# FPGA_MIO.net
KiCad netlist of a schematic drawn in Altium Designer
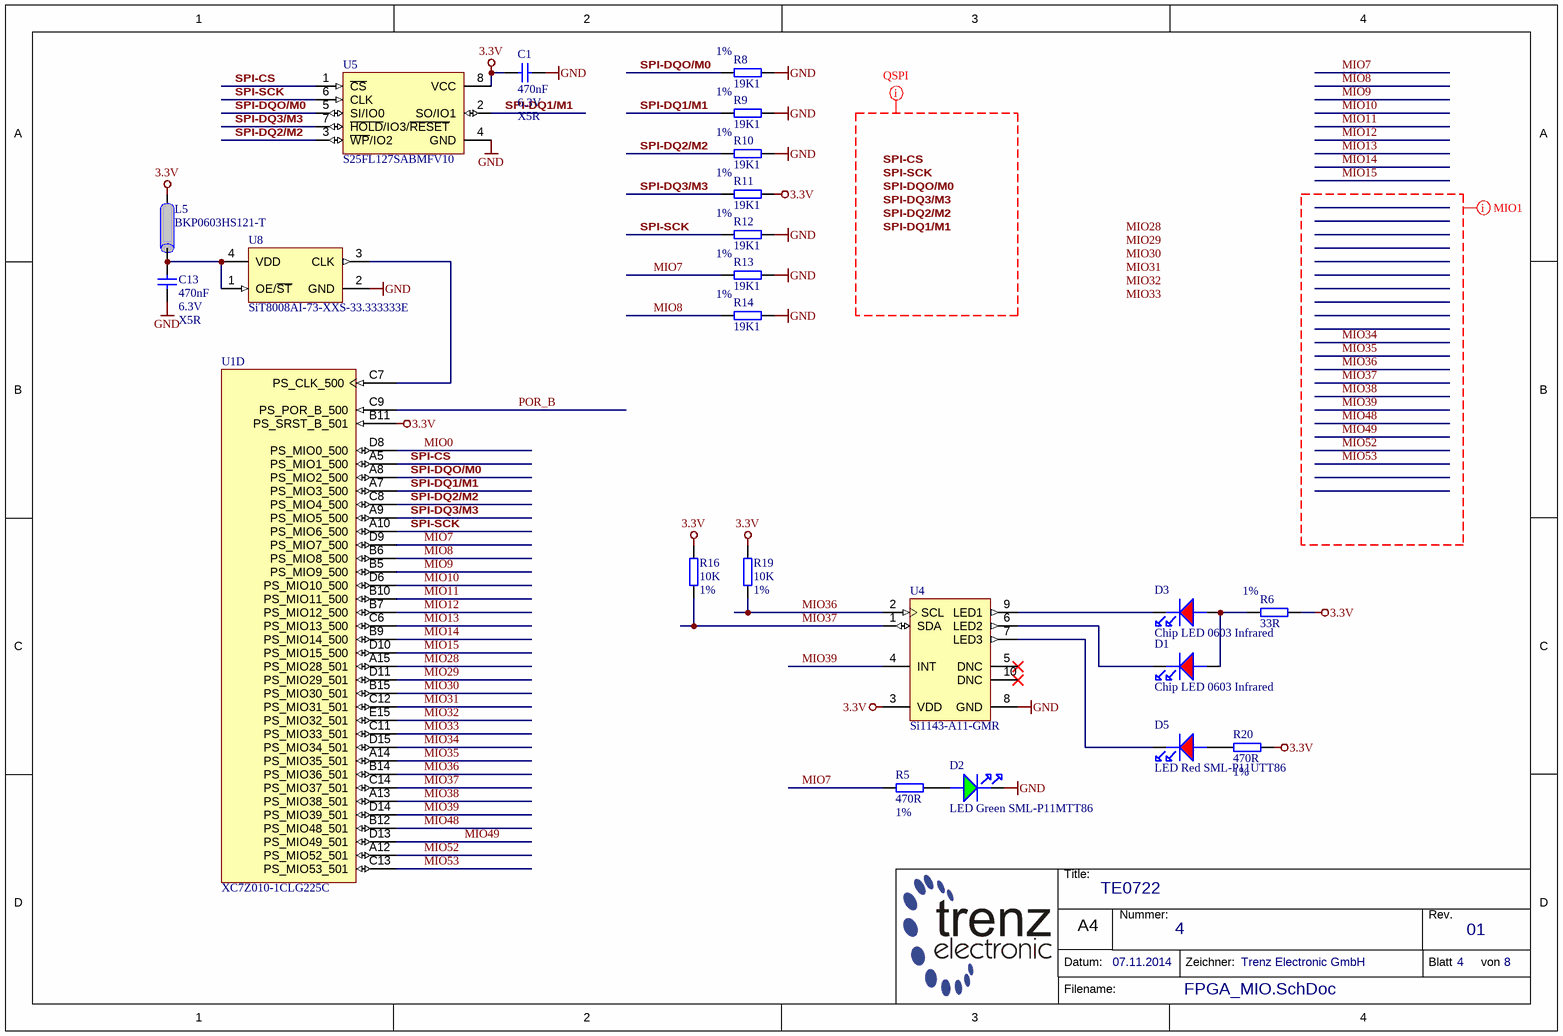
[diagram p0: FPGA_MIO.SchDoc]

(export (version "E")
  (design (tool "Eeschema 10.0.6"))
  (components
    (comp (ref "C1")
      (value "470nF")
      (footprint "CAPC0603X33N")
      (description "KON 470nF X5R 6.3V SMD 20%")
      (fields
        (field (name "VOLTAGE") "6.3V")
        (field (name "TECHNOLOGY") "X5R")
        (field (name "TOLERANCE") "20%")
      )
      (libsource (lib "TE") (part "CAP-NP"))
    )
    (comp (ref "C13")
      (value "470nF")
      (footprint "CAPC0603X33N")
      (description "KON 470nF X5R 6.3V SMD 20%")
      (fields
        (field (name "VOLTAGE") "6.3V")
        (field (name "TECHNOLOGY") "X5R")
        (field (name "TOLERANCE") "20%")
      )
      (libsource (lib "TE") (part "CAP-NP"))
    )
    (comp (ref "D1")
      (value "Chip LED 0603 Infrared")
      (footprint "chipLED_0603_Red")
      (fields (field (name "VOLTAGE") "1.2"))
      (libsource (lib "TE") (part "LED_ROT"))
    )
    (comp (ref "D2")
      (value "LED Green SML-P11MTT86")
      (footprint "LEDC1006X25N_GREEN")
      (description "LED Grün SML-P11MTT86 SMD")
      (libsource (lib "TE") (part "LED_GRUEN"))
    )
    (comp (ref "D3")
      (value "Chip LED 0603 Infrared")
      (footprint "chipLED_0603_Red")
      (fields (field (name "VOLTAGE") "1.2"))
      (libsource (lib "TE") (part "LED_ROT"))
    )
    (comp (ref "D5")
      (value "LED Red SML-P11UTT86")
      (footprint "LEDC1006X25N_RED")
      (description "LED Rot SML-P11UTT86 SMD")
      (libsource (lib "TE") (part "LED_ROT"))
    )
    (comp (ref "L5")
      (value "BKP0603HS121-T")
      (footprint "INDC0603X33N")
      (description "Ferritdurchführung SMD 0201")
      (fields (field (name "TOLERANCE") "25%"))
      (libsource (lib "TE") (part "Ferritperle"))
    )
    (comp (ref "R5")
      (value "470R")
      (footprint "RESC1005X40N")
      (description "WID SMD 470R 1% 0,063W")
      (fields (field (name "TOLERANCE") "1%"))
      (libsource (lib "TE") (part "RES"))
    )
    (comp (ref "R6")
      (value "33R")
      (footprint "RESC1005X40N")
      (description "WID SMD 33R 1% 0,063W")
      (fields (field (name "TOLERANCE") "1%"))
      (libsource (lib "TE") (part "RES"))
    )
    (comp (ref "R8")
      (value "19K1")
      (footprint "RESC0603X26N")
      (description "WID SMD 19K1 1% 0,05W")
      (fields (field (name "TOLERANCE") "1%"))
      (libsource (lib "TE") (part "RES"))
    )
    (comp (ref "R9")
      (value "19K1")
      (footprint "RESC0603X26N")
      (description "WID SMD 19K1 1% 0,05W")
      (fields (field (name "TOLERANCE") "1%"))
      (libsource (lib "TE") (part "RES"))
    )
    (comp (ref "R10")
      (value "19K1")
      (footprint "RESC0603X26N")
      (description "WID SMD 19K1 1% 0,05W")
      (fields (field (name "TOLERANCE") "1%"))
      (libsource (lib "TE") (part "RES"))
    )
    (comp (ref "R11")
      (value "19K1")
      (footprint "RESC0603X26N")
      (description "WID SMD 19K1 1% 0,05W")
      (fields (field (name "TOLERANCE") "1%"))
      (libsource (lib "TE") (part "RES"))
    )
    (comp (ref "R12")
      (value "19K1")
      (footprint "RESC0603X26N")
      (description "WID SMD 19K1 1% 0,05W")
      (fields (field (name "TOLERANCE") "1%"))
      (libsource (lib "TE") (part "RES"))
    )
    (comp (ref "R13")
      (value "19K1")
      (footprint "RESC0603X26N")
      (description "WID SMD 19K1 1% 0,05W")
      (fields (field (name "TOLERANCE") "1%"))
      (libsource (lib "TE") (part "RES"))
    )
    (comp (ref "R14")
      (value "19K1")
      (footprint "RESC0603X26N")
      (description "WID SMD 19K1 1% 0,05W")
      (fields (field (name "TOLERANCE") "1%"))
      (libsource (lib "TE") (part "RES"))
    )
    (comp (ref "R16")
      (value "10K")
      (footprint "RESC0603X26N")
      (description "WID SMD 10K 1% 0,05W")
      (fields (field (name "TOLERANCE") "1%"))
      (libsource (lib "TE") (part "RES"))
    )
    (comp (ref "R19")
      (value "10K")
      (footprint "RESC0603X26N")
      (description "WID SMD 10K 1% 0,05W")
      (fields (field (name "TOLERANCE") "1%"))
      (libsource (lib "TE") (part "RES"))
    )
    (comp (ref "R20")
      (value "470R")
      (footprint "RESC1005X40N")
      (description "WID SMD 470R 1% 0,063W")
      (fields (field (name "TOLERANCE") "1%"))
      (libsource (lib "TE") (part "RES"))
    )
    (comp (ref "U1")
      (value "XC7Z010-1CLG225C")
      (footprint "CLG225")
      (libsource (lib "TE") (part "XC7Z010-CLG225"))
    )
    (comp (ref "U4")
      (value "Si1143-A11-GMR")
      (footprint "QFN50P200X200X75-10N")
      (libsource (lib "TE") (part "Si1143"))
    )
    (comp (ref "U5")
      (value "S25FL127SABMFV10")
      (footprint "SOIC127P790X216-8N")
      (description "S25FL127SABMFV10 automotive SO8")
      (libsource (lib "TE") (part "S25FL127S-SO8"))
    )
    (comp (ref "U8")
      (value "SiT8008AI-73-XXS-33.333333E")
      (footprint "2016")
      (description "SiT8008AI-73-XXS-33.333333E MEMS Oszillator 33.333333MHz")
      (libsource (lib "TE") (part "SiT8103"))
    )
  )
  (nets
    (net (code "1") (name "/MIO0") (class "Default")
      (node (ref "U1") (pin "D8") (pinfunction "PS_MIO0_500_D8") (pintype "bidirectional"))
    )
    (net (code "2") (name "/MIO7") (class "Default")
      (node (ref "R13") (pin "1") (pinfunction "1_1") (pintype "passive"))
      (node (ref "R5") (pin "2") (pinfunction "2_2") (pintype "passive"))
      (node (ref "U1") (pin "D9") (pinfunction "PS_MIO7_500_D9") (pintype "bidirectional"))
    )
    (net (code "3") (name "/MIO8") (class "Default")
      (node (ref "R14") (pin "1") (pinfunction "1_1") (pintype "passive"))
      (node (ref "U1") (pin "B6") (pinfunction "PS_MIO8_500_B6") (pintype "bidirectional"))
    )
    (net (code "4") (name "/MIO9") (class "Default")
      (node (ref "U1") (pin "B5") (pinfunction "PS_MIO9_500_B5") (pintype "bidirectional"))
    )
    (net (code "5") (name "/MIO10") (class "Default")
      (node (ref "U1") (pin "D6") (pinfunction "PS_MIO10_500_D6") (pintype "bidirectional"))
    )
    (net (code "6") (name "/MIO11") (class "Default")
      (node (ref "U1") (pin "B10") (pinfunction "PS_MIO11_500_B10") (pintype "bidirectional"))
    )
    (net (code "7") (name "/MIO12") (class "Default")
      (node (ref "U1") (pin "B7") (pinfunction "PS_MIO12_500_B7") (pintype "bidirectional"))
    )
    (net (code "8") (name "/MIO13") (class "Default")
      (node (ref "U1") (pin "C6") (pinfunction "PS_MIO13_500_C6") (pintype "bidirectional"))
    )
    (net (code "9") (name "/MIO14") (class "Default")
      (node (ref "U1") (pin "B9") (pinfunction "PS_MIO14_500_B9") (pintype "bidirectional"))
    )
    (net (code "10") (name "/MIO15") (class "Default")
      (node (ref "U1") (pin "D10") (pinfunction "PS_MIO15_500_D10") (pintype "bidirectional"))
    )
    (net (code "11") (name "/MIO28") (class "Default")
      (node (ref "U1") (pin "A15") (pinfunction "PS_MIO28_501_A15") (pintype "bidirectional"))
    )
    (net (code "12") (name "/MIO29") (class "Default")
      (node (ref "U1") (pin "D11") (pinfunction "PS_MIO29_501_D11") (pintype "bidirectional"))
    )
    (net (code "13") (name "/MIO30") (class "Default")
      (node (ref "U1") (pin "B15") (pinfunction "PS_MIO30_501_B15") (pintype "bidirectional"))
    )
    (net (code "14") (name "/MIO31") (class "Default")
      (node (ref "U1") (pin "C12") (pinfunction "PS_MIO31_501_C12") (pintype "bidirectional"))
    )
    (net (code "15") (name "/MIO32") (class "Default")
      (node (ref "U1") (pin "E15") (pinfunction "PS_MIO32_501_E15") (pintype "bidirectional"))
    )
    (net (code "16") (name "/MIO33") (class "Default")
      (node (ref "U1") (pin "C11") (pinfunction "PS_MIO33_501_C11") (pintype "bidirectional"))
    )
    (net (code "17") (name "/MIO34") (class "Default")
      (node (ref "U1") (pin "D15") (pinfunction "PS_MIO34_501_D15") (pintype "bidirectional"))
    )
    (net (code "18") (name "/MIO35") (class "Default")
      (node (ref "U1") (pin "A14") (pinfunction "PS_MIO35_501_A14") (pintype "bidirectional"))
    )
    (net (code "19") (name "/MIO36") (class "Default")
      (node (ref "R19") (pin "1") (pinfunction "1_1") (pintype "passive"))
      (node (ref "U1") (pin "B14") (pinfunction "PS_MIO36_501_B14") (pintype "bidirectional"))
      (node (ref "U4") (pin "2") (pinfunction "SCL_2") (pintype "input"))
    )
    (net (code "20") (name "/MIO37") (class "Default")
      (node (ref "R16") (pin "1") (pinfunction "1_1") (pintype "passive"))
      (node (ref "U1") (pin "C14") (pinfunction "PS_MIO37_501_C14") (pintype "bidirectional"))
      (node (ref "U4") (pin "1") (pinfunction "SDA_1") (pintype "bidirectional"))
    )
    (net (code "21") (name "/MIO38") (class "Default")
      (node (ref "U1") (pin "A13") (pinfunction "PS_MIO38_501_A13") (pintype "bidirectional"))
    )
    (net (code "22") (name "/MIO39") (class "Default")
      (node (ref "U1") (pin "D14") (pinfunction "PS_MIO39_501_D14") (pintype "bidirectional"))
      (node (ref "U4") (pin "4") (pinfunction "INT_4") (pintype "open_collector"))
    )
    (net (code "23") (name "/MIO48") (class "Default")
      (node (ref "U1") (pin "B12") (pinfunction "PS_MIO48_501_B12") (pintype "bidirectional"))
    )
    (net (code "24") (name "/MIO49") (class "Default")
      (node (ref "U1") (pin "D13") (pinfunction "PS_MIO49_501_D13") (pintype "bidirectional"))
    )
    (net (code "25") (name "/MIO52") (class "Default")
      (node (ref "U1") (pin "A12") (pinfunction "PS_MIO52_501_A12") (pintype "bidirectional"))
    )
    (net (code "26") (name "/MIO53") (class "Default")
      (node (ref "U1") (pin "C13") (pinfunction "PS_MIO53_501_C13") (pintype "bidirectional"))
    )
    (net (code "27") (name "/POR_B") (class "Default")
      (node (ref "U1") (pin "C9") (pinfunction "PS_POR_B_500_C9") (pintype "input"))
    )
    (net (code "28") (name "/SPI-CS") (class "Default")
      (node (ref "U1") (pin "A5") (pinfunction "PS_MIO1_500_A5") (pintype "bidirectional"))
      (node (ref "U5") (pin "1") (pinfunction "~{CS}_1") (pintype "input"))
    )
    (net (code "29") (name "/SPI-DQ1{slash}M1") (class "Default")
      (node (ref "R9") (pin "1") (pinfunction "1_1") (pintype "passive"))
      (node (ref "U1") (pin "A7") (pinfunction "PS_MIO3_500_A7") (pintype "bidirectional"))
      (node (ref "U5") (pin "2") (pinfunction "SO/IO1_2") (pintype "bidirectional"))
    )
    (net (code "30") (name "/SPI-DQ2{slash}M2") (class "Default")
      (node (ref "R10") (pin "1") (pinfunction "1_1") (pintype "passive"))
      (node (ref "U1") (pin "C8") (pinfunction "PS_MIO4_500_C8") (pintype "bidirectional"))
      (node (ref "U5") (pin "3") (pinfunction "~{WP}/IO2_3") (pintype "bidirectional"))
    )
    (net (code "31") (name "/SPI-DQ3{slash}M3") (class "Default")
      (node (ref "R11") (pin "1") (pinfunction "1_1") (pintype "passive"))
      (node (ref "U1") (pin "A9") (pinfunction "PS_MIO5_500_A9") (pintype "bidirectional"))
      (node (ref "U5") (pin "7") (pinfunction "~{HOLD}/IO3/~{RESET}_7") (pintype "bidirectional"))
    )
    (net (code "32") (name "/SPI-DQO{slash}M0") (class "Default")
      (node (ref "R8") (pin "1") (pinfunction "1_1") (pintype "passive"))
      (node (ref "U1") (pin "A8") (pinfunction "PS_MIO2_500_A8") (pintype "bidirectional"))
      (node (ref "U5") (pin "5") (pinfunction "SI/IO0_5") (pintype "bidirectional"))
    )
    (net (code "33") (name "/SPI-SCK") (class "Default")
      (node (ref "R12") (pin "1") (pinfunction "1_1") (pintype "passive"))
      (node (ref "U1") (pin "A10") (pinfunction "PS_MIO6_500_A10") (pintype "bidirectional"))
      (node (ref "U5") (pin "6") (pinfunction "CLK_6") (pintype "input"))
    )
    (net (code "34") (name "3.3V") (class "Default")
      (node (ref "C1") (pin "1") (pinfunction "1_1") (pintype "passive"))
      (node (ref "L5") (pin "1") (pinfunction "1_1") (pintype "passive"))
      (node (ref "R11") (pin "2") (pinfunction "2_2") (pintype "passive"))
      (node (ref "R16") (pin "2") (pinfunction "2_2") (pintype "passive"))
      (node (ref "R19") (pin "2") (pinfunction "2_2") (pintype "passive"))
      (node (ref "R20") (pin "1") (pinfunction "1_1") (pintype "passive"))
      (node (ref "R6") (pin "2") (pinfunction "2_2") (pintype "passive"))
      (node (ref "U1") (pin "B11") (pinfunction "PS_SRST_B_501_B11") (pintype "input"))
      (node (ref "U4") (pin "3") (pinfunction "VDD_3") (pintype "power_in"))
      (node (ref "U5") (pin "8") (pinfunction "VCC_8") (pintype "power_in"))
    )
    (net (code "35") (name "GND") (class "Default")
      (node (ref "C1") (pin "2") (pinfunction "2_2") (pintype "passive"))
      (node (ref "C13") (pin "2") (pinfunction "2_2") (pintype "passive"))
      (node (ref "D2") (pin "K") (pinfunction "K_K") (pintype "passive"))
      (node (ref "R10") (pin "2") (pinfunction "2_2") (pintype "passive"))
      (node (ref "R12") (pin "2") (pinfunction "2_2") (pintype "passive"))
      (node (ref "R13") (pin "2") (pinfunction "2_2") (pintype "passive"))
      (node (ref "R14") (pin "2") (pinfunction "2_2") (pintype "passive"))
      (node (ref "R8") (pin "2") (pinfunction "2_2") (pintype "passive"))
      (node (ref "R9") (pin "2") (pinfunction "2_2") (pintype "passive"))
      (node (ref "U4") (pin "8") (pinfunction "GND_8") (pintype "power_in"))
      (node (ref "U5") (pin "4") (pinfunction "GND_4") (pintype "power_in"))
      (node (ref "U8") (pin "2") (pinfunction "GND_2") (pintype "power_in"))
    )
    (net (code "36") (name "Net-(D1-PadA)") (class "Default")
      (node (ref "D1") (pin "A") (pinfunction "A_A") (pintype "passive"))
      (node (ref "D3") (pin "A") (pinfunction "A_A") (pintype "passive"))
      (node (ref "R6") (pin "1") (pinfunction "1_1") (pintype "passive"))
    )
    (net (code "37") (name "Net-(D2-PadA)") (class "Default")
      (node (ref "D2") (pin "A") (pinfunction "A_A") (pintype "passive"))
      (node (ref "R5") (pin "1") (pinfunction "1_1") (pintype "passive"))
    )
    (net (code "38") (name "Net-(D5-PadA)") (class "Default")
      (node (ref "D5") (pin "A") (pinfunction "A_A") (pintype "passive"))
      (node (ref "R20") (pin "2") (pinfunction "2_2") (pintype "passive"))
    )
    (net (code "39") (name "Net-(U1D-PS_CLK_500)") (class "Default")
      (node (ref "U1") (pin "C7") (pinfunction "PS_CLK_500_C7") (pintype "input"))
      (node (ref "U8") (pin "3") (pinfunction "CLK_3") (pintype "output"))
    )
    (net (code "40") (name "Net-(U4-LED1)") (class "Default")
      (node (ref "D3") (pin "K") (pinfunction "K_K") (pintype "passive"))
      (node (ref "U4") (pin "9") (pinfunction "LED1_9") (pintype "output"))
    )
    (net (code "41") (name "Net-(U4-LED2)") (class "Default")
      (node (ref "D1") (pin "K") (pinfunction "K_K") (pintype "passive"))
      (node (ref "U4") (pin "6") (pinfunction "LED2_6") (pintype "output"))
    )
    (net (code "42") (name "Net-(U4-LED3)") (class "Default")
      (node (ref "D5") (pin "K") (pinfunction "K_K") (pintype "passive"))
      (node (ref "U4") (pin "7") (pinfunction "LED3_7") (pintype "output"))
    )
    (net (code "43") (name "Net-(U8-OE{slash}~{ST})") (class "Default")
      (node (ref "C13") (pin "1") (pinfunction "1_1") (pintype "passive"))
      (node (ref "L5") (pin "2") (pinfunction "2_2") (pintype "passive"))
      (node (ref "U8") (pin "1") (pinfunction "OE/~{ST}_1") (pintype "input"))
      (node (ref "U8") (pin "4") (pinfunction "VDD_4") (pintype "power_in"))
    )
    (net (code "44") (name "unconnected-(U4-DNC-Pad5)") (class "Default")
      (node (ref "U4") (pin "5") (pinfunction "DNC_5") (pintype "passive+no_connect"))
    )
    (net (code "45") (name "unconnected-(U4-DNC-Pad10)") (class "Default")
      (node (ref "U4") (pin "10") (pinfunction "DNC_10") (pintype "passive+no_connect"))
    )
  )
)
